# Main.net
KiCad netlist of a schematic drawn in Altium Designer
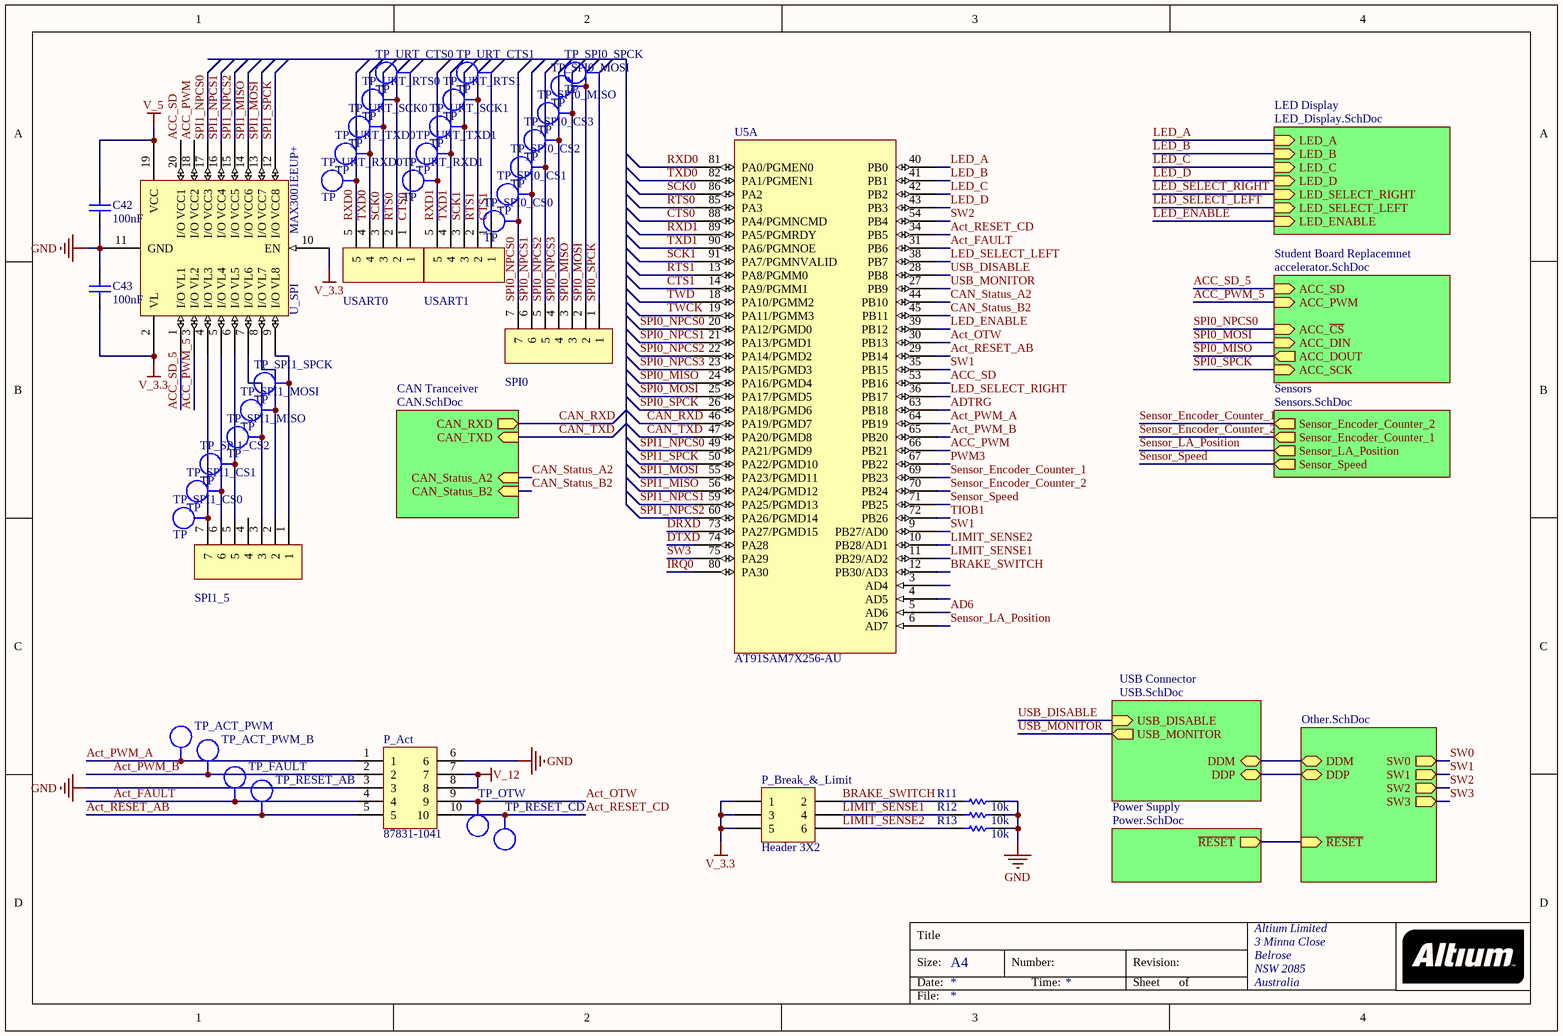
[diagram p0: Main.SchDoc]

(export (version "E")
  (design (tool "Eeschema 10.0.6"))
  (components
    (comp (ref "C42")
      (value "100nF")
      (footprint "0603")
      (description "CAP CER .10UF 50V X5R 0603")
      (fields (field (name "MANUFACTURER") "Taiyo Yuden") (field (name "PART NUMBER") "CP_100nF 0603"))
      (libsource (lib "ENEL429_4") (part "CP_100nF 0603"))
    )
    (comp (ref "C43")
      (value "100nF")
      (footprint "0603")
      (description "CAP CER .10UF 50V X5R 0603")
      (fields (field (name "MANUFACTURER") "Taiyo Yuden") (field (name "PART NUMBER") "CP_100nF 0603"))
      (libsource (lib "ENEL429_4") (part "CP_100nF 0603"))
    )
    (comp (ref "P_Act")
      (value "87831-1041")
      (footprint "87831-1041")
      (description "HEADER MALE 10POS VERT W/LOCK")
      (fields (field (name "MANUFACTURER") "Molex"))
      (libsource (lib "MarioLib") (part "87831-1041"))
    )
    (comp (ref "P_Break_&_Limit")
      (value "Header 3X2")
      (footprint "HDR2X3")
      (description "Header, 3-Pin, Dual row")
      (fields (field (name "PUBLISHER") "Altium Limited"))
      (libsource (lib "Miscellaneous Connectors") (part "Header 3X2"))
    )
    (comp (ref "R11")
      (value "10k")
      (footprint "0603")
      (description "RES 10.0K OHM 1/10W 1% 0603 SMD")
      (fields (field (name "MANUFACTURER") "Yageo") (field (name "PART NUMBER") "RS_10k 0603"))
      (libsource (lib "ENEL429_4") (part "RS_10k 0603"))
    )
    (comp (ref "R12")
      (value "10k")
      (footprint "0603")
      (description "RES 10.0K OHM 1/10W 1% 0603 SMD")
      (fields (field (name "MANUFACTURER") "Yageo") (field (name "PART NUMBER") "RS_10k 0603"))
      (libsource (lib "ENEL429_4") (part "RS_10k 0603"))
    )
    (comp (ref "R13")
      (value "10k")
      (footprint "0603")
      (description "RES 10.0K OHM 1/10W 1% 0603 SMD")
      (fields (field (name "MANUFACTURER") "Yageo") (field (name "PART NUMBER") "RS_10k 0603"))
      (libsource (lib "ENEL429_4") (part "RS_10k 0603"))
    )
    (comp (ref "SPI0")
      (value "53261-0771")
      (footprint "53261-0771")
      (description "7-pin PicoBlade Right-angle Header")
      (fields (field (name "MANUFACTURER") "Molex"))
      (libsource (lib "MarioLib") (part "53261-0771"))
    )
    (comp (ref "SPI1_5")
      (value "53261-0771")
      (footprint "53261-0771")
      (description "7-pin PicoBlade Right-angle Header")
      (fields (field (name "MANUFACTURER") "Molex"))
      (libsource (lib "MarioLib") (part "53261-0771"))
    )
    (comp (ref "TP_ACT_PWM")
      (value "TP")
      (footprint "TEST_POINT_4X2MM")
      (description "Test-Point")
      (fields (field (name "PART NUMBER") "TP_TESTPOINT"))
      (libsource (lib "ENEL429_4") (part "TP_TESTPOINT"))
    )
    (comp (ref "TP_ACT_PWM_B")
      (value "TP")
      (footprint "TEST_POINT_4X2MM")
      (description "Test-Point")
      (fields (field (name "PART NUMBER") "TP_TESTPOINT"))
      (libsource (lib "ENEL429_4") (part "TP_TESTPOINT"))
    )
    (comp (ref "TP_FAULT")
      (value "TP")
      (footprint "TEST_POINT_4X2MM")
      (description "Test-Point")
      (fields (field (name "PART NUMBER") "TP_TESTPOINT"))
      (libsource (lib "ENEL429_4") (part "TP_TESTPOINT"))
    )
    (comp (ref "TP_OTW")
      (value "TP")
      (footprint "TEST_POINT_4X2MM")
      (description "Test-Point")
      (fields (field (name "PART NUMBER") "TP_TESTPOINT"))
      (libsource (lib "ENEL429_4") (part "TP_TESTPOINT"))
    )
    (comp (ref "TP_RESET_AB")
      (value "TP")
      (footprint "TEST_POINT_4X2MM")
      (description "Test-Point")
      (fields (field (name "PART NUMBER") "TP_TESTPOINT"))
      (libsource (lib "ENEL429_4") (part "TP_TESTPOINT"))
    )
    (comp (ref "TP_RESET_CD")
      (value "TP")
      (footprint "TEST_POINT_4X2MM")
      (description "Test-Point")
      (fields (field (name "PART NUMBER") "TP_TESTPOINT"))
      (libsource (lib "ENEL429_4") (part "TP_TESTPOINT"))
    )
    (comp (ref "TP_SPI0_CS0")
      (value "TP")
      (footprint "TEST_POINT_4X2MM")
      (description "Test-Point")
      (fields (field (name "PART NUMBER") "TP_TESTPOINT"))
      (libsource (lib "ENEL429_4") (part "TP_TESTPOINT"))
    )
    (comp (ref "TP_SPI0_CS1")
      (value "TP")
      (footprint "TEST_POINT_4X2MM")
      (description "Test-Point")
      (fields (field (name "PART NUMBER") "TP_TESTPOINT"))
      (libsource (lib "ENEL429_4") (part "TP_TESTPOINT"))
    )
    (comp (ref "TP_SPI0_CS2")
      (value "TP")
      (footprint "TEST_POINT_4X2MM")
      (description "Test-Point")
      (fields (field (name "PART NUMBER") "TP_TESTPOINT"))
      (libsource (lib "ENEL429_4") (part "TP_TESTPOINT"))
    )
    (comp (ref "TP_SPI0_CS3")
      (value "TP")
      (footprint "TEST_POINT_4X2MM")
      (description "Test-Point")
      (fields (field (name "PART NUMBER") "TP_TESTPOINT"))
      (libsource (lib "ENEL429_4") (part "TP_TESTPOINT"))
    )
    (comp (ref "TP_SPI0_MISO")
      (value "TP")
      (footprint "TEST_POINT_4X2MM")
      (description "Test-Point")
      (fields (field (name "PART NUMBER") "TP_TESTPOINT"))
      (libsource (lib "ENEL429_4") (part "TP_TESTPOINT"))
    )
    (comp (ref "TP_SPI0_MOSI")
      (value "TP")
      (footprint "TEST_POINT_4X2MM")
      (description "Test-Point")
      (fields (field (name "PART NUMBER") "TP_TESTPOINT"))
      (libsource (lib "ENEL429_4") (part "TP_TESTPOINT"))
    )
    (comp (ref "TP_SPI0_SPCK")
      (value "TP")
      (footprint "TEST_POINT_4X2MM")
      (description "Test-Point")
      (fields (field (name "PART NUMBER") "TP_TESTPOINT"))
      (libsource (lib "ENEL429_4") (part "TP_TESTPOINT"))
    )
    (comp (ref "TP_SPI1_CS0")
      (value "TP")
      (footprint "TEST_POINT_4X2MM")
      (description "Test-Point")
      (fields (field (name "PART NUMBER") "TP_TESTPOINT"))
      (libsource (lib "ENEL429_4") (part "TP_TESTPOINT"))
    )
    (comp (ref "TP_SPI1_CS1")
      (value "TP")
      (footprint "TEST_POINT_4X2MM")
      (description "Test-Point")
      (fields (field (name "PART NUMBER") "TP_TESTPOINT"))
      (libsource (lib "ENEL429_4") (part "TP_TESTPOINT"))
    )
    (comp (ref "TP_SPI1_CS2")
      (value "TP")
      (footprint "TEST_POINT_4X2MM")
      (description "Test-Point")
      (fields (field (name "PART NUMBER") "TP_TESTPOINT"))
      (libsource (lib "ENEL429_4") (part "TP_TESTPOINT"))
    )
    (comp (ref "TP_SPI1_MISO")
      (value "TP")
      (footprint "TEST_POINT_4X2MM")
      (description "Test-Point")
      (fields (field (name "PART NUMBER") "TP_TESTPOINT"))
      (libsource (lib "ENEL429_4") (part "TP_TESTPOINT"))
    )
    (comp (ref "TP_SPI1_MOSI")
      (value "TP")
      (footprint "TEST_POINT_4X2MM")
      (description "Test-Point")
      (fields (field (name "PART NUMBER") "TP_TESTPOINT"))
      (libsource (lib "ENEL429_4") (part "TP_TESTPOINT"))
    )
    (comp (ref "TP_SPI1_SPCK")
      (value "TP")
      (footprint "TEST_POINT_4X2MM")
      (description "Test-Point")
      (fields (field (name "PART NUMBER") "TP_TESTPOINT"))
      (libsource (lib "ENEL429_4") (part "TP_TESTPOINT"))
    )
    (comp (ref "TP_URT_CTS0")
      (value "TP")
      (footprint "TEST_POINT_4X2MM")
      (description "Test-Point")
      (fields (field (name "PART NUMBER") "TP_TESTPOINT"))
      (libsource (lib "ENEL429_4") (part "TP_TESTPOINT"))
    )
    (comp (ref "TP_URT_CTS1")
      (value "TP")
      (footprint "TEST_POINT_4X2MM")
      (description "Test-Point")
      (fields (field (name "PART NUMBER") "TP_TESTPOINT"))
      (libsource (lib "ENEL429_4") (part "TP_TESTPOINT"))
    )
    (comp (ref "TP_URT_RTS0")
      (value "TP")
      (footprint "TEST_POINT_4X2MM")
      (description "Test-Point")
      (fields (field (name "PART NUMBER") "TP_TESTPOINT"))
      (libsource (lib "ENEL429_4") (part "TP_TESTPOINT"))
    )
    (comp (ref "TP_URT_RTS1")
      (value "TP")
      (footprint "TEST_POINT_4X2MM")
      (description "Test-Point")
      (fields (field (name "PART NUMBER") "TP_TESTPOINT"))
      (libsource (lib "ENEL429_4") (part "TP_TESTPOINT"))
    )
    (comp (ref "TP_URT_RXD0")
      (value "TP")
      (footprint "TEST_POINT_4X2MM")
      (description "Test-Point")
      (fields (field (name "PART NUMBER") "TP_TESTPOINT"))
      (libsource (lib "ENEL429_4") (part "TP_TESTPOINT"))
    )
    (comp (ref "TP_URT_RXD1")
      (value "TP")
      (footprint "TEST_POINT_4X2MM")
      (description "Test-Point")
      (fields (field (name "PART NUMBER") "TP_TESTPOINT"))
      (libsource (lib "ENEL429_4") (part "TP_TESTPOINT"))
    )
    (comp (ref "TP_URT_SCK0")
      (value "TP")
      (footprint "TEST_POINT_4X2MM")
      (description "Test-Point")
      (fields (field (name "PART NUMBER") "TP_TESTPOINT"))
      (libsource (lib "ENEL429_4") (part "TP_TESTPOINT"))
    )
    (comp (ref "TP_URT_SCK1")
      (value "TP")
      (footprint "TEST_POINT_4X2MM")
      (description "Test-Point")
      (fields (field (name "PART NUMBER") "TP_TESTPOINT"))
      (libsource (lib "ENEL429_4") (part "TP_TESTPOINT"))
    )
    (comp (ref "TP_URT_TXD0")
      (value "TP")
      (footprint "TEST_POINT_4X2MM")
      (description "Test-Point")
      (fields (field (name "PART NUMBER") "TP_TESTPOINT"))
      (libsource (lib "ENEL429_4") (part "TP_TESTPOINT"))
    )
    (comp (ref "TP_URT_TXD1")
      (value "TP")
      (footprint "TEST_POINT_4X2MM")
      (description "Test-Point")
      (fields (field (name "PART NUMBER") "TP_TESTPOINT"))
      (libsource (lib "ENEL429_4") (part "TP_TESTPOINT"))
    )
    (comp (ref "U5")
      (value "AT91SAM7X256-AU")
      (footprint "LQFP100_N")
      (description "ARM7TDMI 32-Bit RISC CPU 256KB Flash and 64KB SRAM")
      (fields
        (field (name "MANAFACTURE PART NUMBER") "AT91SAM7XC256B-AU")
        (field (name "PUBLISHER") "Altium Limited")
      )
      (libsource (lib "Atmel Microcontroller 32-Bit ARM") (part "AT91SAM7X256-AU"))
    )
    (comp (ref "USART0")
      (value "53261-0571")
      (footprint "53261-0571")
      (description "5-pin PicoBlade Right-angle Header")
      (fields (field (name "MANUFACTURER") "Molex"))
      (libsource (lib "MarioLib") (part "53261-0571"))
    )
    (comp (ref "USART1")
      (value "53261-0571")
      (footprint "53261-0571")
      (description "5-pin PicoBlade Right-angle Header")
      (fields (field (name "MANUFACTURER") "Molex"))
      (libsource (lib "MarioLib") (part "53261-0571"))
    )
    (comp (ref "U_SPI")
      (value "MAX3001EEUP+")
      (footprint "TSOP65P640X110-20N")
      (libsource (lib "MarioLib") (part "MAX3001EEUP+"))
    )
  )
  (nets
    (net (code "1") (name "/ACC_PWM") (class "Default")
      (node (ref "U5") (pin "66") (pinfunction "PB21_66") (pintype "bidirectional"))
      (node (ref "U_SPI") (pin "18") (pinfunction "I/O_VCC2_18") (pintype "bidirectional"))
    )
    (net (code "2") (name "/ACC_PWM_5") (class "Default")
      (node (ref "U_SPI") (pin "3") (pinfunction "I/O_VL2_3") (pintype "bidirectional"))
    )
    (net (code "3") (name "/ACC_SD") (class "Default")
      (node (ref "U5") (pin "53") (pinfunction "PB16_53") (pintype "bidirectional"))
      (node (ref "U_SPI") (pin "20") (pinfunction "I/O_VCC1_20") (pintype "bidirectional"))
    )
    (net (code "4") (name "/ACC_SD_5") (class "Default")
      (node (ref "U_SPI") (pin "1") (pinfunction "I/O_VL1_1") (pintype "bidirectional"))
    )
    (net (code "5") (name "/AD6") (class "Default")
      (node (ref "U5") (pin "5") (pinfunction "AD6_5") (pintype "input"))
    )
    (net (code "6") (name "/ADTRG") (class "Default")
      (node (ref "U5") (pin "63") (pinfunction "PB18_63") (pintype "bidirectional"))
    )
    (net (code "7") (name "/Act_FAULT") (class "Default")
      (node (ref "P_Act") (pin "4") (pinfunction "4_4") (pintype "passive"))
      (node (ref "TP_FAULT") (pin "1") (pinfunction "1_1") (pintype "passive"))
      (node (ref "U5") (pin "31") (pinfunction "PB6_31") (pintype "bidirectional"))
    )
    (net (code "8") (name "/Act_OTW") (class "Default")
      (node (ref "P_Act") (pin "9") (pinfunction "9_9") (pintype "passive"))
      (node (ref "TP_OTW") (pin "1") (pinfunction "1_1") (pintype "passive"))
      (node (ref "U5") (pin "30") (pinfunction "PB13_30") (pintype "bidirectional"))
    )
    (net (code "9") (name "/Act_PWM_A") (class "Default")
      (node (ref "P_Act") (pin "1") (pinfunction "1_1") (pintype "passive"))
      (node (ref "TP_ACT_PWM") (pin "1") (pinfunction "1_1") (pintype "passive"))
      (node (ref "U5") (pin "64") (pinfunction "PB19_64") (pintype "bidirectional"))
    )
    (net (code "10") (name "/Act_PWM_B") (class "Default")
      (node (ref "P_Act") (pin "2") (pinfunction "2_2") (pintype "passive"))
      (node (ref "TP_ACT_PWM_B") (pin "1") (pinfunction "1_1") (pintype "passive"))
      (node (ref "U5") (pin "65") (pinfunction "PB20_65") (pintype "bidirectional"))
    )
    (net (code "11") (name "/Act_RESET_AB") (class "Default")
      (node (ref "P_Act") (pin "5") (pinfunction "5_5") (pintype "passive"))
      (node (ref "TP_RESET_AB") (pin "1") (pinfunction "1_1") (pintype "passive"))
      (node (ref "U5") (pin "29") (pinfunction "PB14_29") (pintype "bidirectional"))
    )
    (net (code "12") (name "/Act_RESET_CD") (class "Default")
      (node (ref "P_Act") (pin "10") (pinfunction "10_10") (pintype "passive"))
      (node (ref "TP_RESET_CD") (pin "1") (pinfunction "1_1") (pintype "passive"))
      (node (ref "U5") (pin "34") (pinfunction "PB5_34") (pintype "bidirectional"))
    )
    (net (code "13") (name "/BRAKE_SWITCH") (class "Default")
      (node (ref "P_Break_&_Limit") (pin "2") (pinfunction "2_2") (pintype "passive"))
      (node (ref "R11") (pin "1") (pinfunction "1_1") (pintype "passive"))
      (node (ref "U5") (pin "12") (pinfunction "PB30/AD3_12") (pintype "bidirectional"))
    )
    (net (code "14") (name "/CAN_RXD") (class "Default")
      (node (ref "U5") (pin "46") (pinfunction "PA19/PGMD7_46") (pintype "bidirectional"))
    )
    (net (code "15") (name "/CAN_Status_A2") (class "Default")
      (node (ref "U5") (pin "44") (pinfunction "PB10_44") (pintype "bidirectional"))
    )
    (net (code "16") (name "/CAN_Status_B2") (class "Default")
      (node (ref "U5") (pin "45") (pinfunction "PB11_45") (pintype "bidirectional"))
    )
    (net (code "17") (name "/CAN_TXD") (class "Default")
      (node (ref "U5") (pin "47") (pinfunction "PA20/PGMD8_47") (pintype "bidirectional"))
    )
    (net (code "18") (name "/CTS0") (class "Default")
      (node (ref "TP_URT_CTS0") (pin "1") (pinfunction "1_1") (pintype "passive"))
      (node (ref "U5") (pin "88") (pinfunction "PA4/PGMNCMD_88") (pintype "bidirectional"))
      (node (ref "USART0") (pin "1") (pinfunction "1_1") (pintype "passive"))
    )
    (net (code "19") (name "/CTS1") (class "Default")
      (node (ref "TP_URT_CTS1") (pin "1") (pinfunction "1_1") (pintype "passive"))
      (node (ref "U5") (pin "14") (pinfunction "PA9/PGMM1_14") (pintype "bidirectional"))
      (node (ref "USART1") (pin "1") (pinfunction "1_1") (pintype "passive"))
    )
    (net (code "22") (name "/DRXD") (class "Default")
      (node (ref "U5") (pin "73") (pinfunction "PA27/PGMD15_73") (pintype "bidirectional"))
    )
    (net (code "23") (name "/DTXD") (class "Default")
      (node (ref "U5") (pin "74") (pinfunction "PA28_74") (pintype "bidirectional"))
    )
    (net (code "24") (name "/IRQ0") (class "Default")
      (node (ref "U5") (pin "80") (pinfunction "PA30_80") (pintype "bidirectional"))
    )
    (net (code "25") (name "/LED_A") (class "Default")
      (node (ref "U5") (pin "40") (pinfunction "PB0_40") (pintype "bidirectional"))
    )
    (net (code "26") (name "/LED_B") (class "Default")
      (node (ref "U5") (pin "41") (pinfunction "PB1_41") (pintype "bidirectional"))
    )
    (net (code "27") (name "/LED_C") (class "Default")
      (node (ref "U5") (pin "42") (pinfunction "PB2_42") (pintype "bidirectional"))
    )
    (net (code "28") (name "/LED_D") (class "Default")
      (node (ref "U5") (pin "43") (pinfunction "PB3_43") (pintype "bidirectional"))
    )
    (net (code "29") (name "/LED_ENABLE") (class "Default")
      (node (ref "U5") (pin "39") (pinfunction "PB12_39") (pintype "bidirectional"))
    )
    (net (code "30") (name "/LED_SELECT_LEFT") (class "Default")
      (node (ref "U5") (pin "38") (pinfunction "PB7_38") (pintype "bidirectional"))
    )
    (net (code "31") (name "/LED_SELECT_RIGHT") (class "Default")
      (node (ref "U5") (pin "36") (pinfunction "PB17_36") (pintype "bidirectional"))
    )
    (net (code "32") (name "/LIMIT_SENSE1") (class "Default")
      (node (ref "P_Break_&_Limit") (pin "4") (pinfunction "4_4") (pintype "passive"))
      (node (ref "R12") (pin "1") (pinfunction "1_1") (pintype "passive"))
      (node (ref "U5") (pin "11") (pinfunction "PB29/AD2_11") (pintype "bidirectional"))
    )
    (net (code "33") (name "/LIMIT_SENSE2") (class "Default")
      (node (ref "P_Break_&_Limit") (pin "6") (pinfunction "6_6") (pintype "passive"))
      (node (ref "R13") (pin "1") (pinfunction "1_1") (pintype "passive"))
      (node (ref "U5") (pin "10") (pinfunction "PB28/AD1_10") (pintype "bidirectional"))
    )
    (net (code "34") (name "/PWM3") (class "Default")
      (node (ref "U5") (pin "67") (pinfunction "PB22_67") (pintype "bidirectional"))
    )
    (net (code "35") (name "/RTS0") (class "Default")
      (node (ref "TP_URT_RTS0") (pin "1") (pinfunction "1_1") (pintype "passive"))
      (node (ref "U5") (pin "85") (pinfunction "PA3_85") (pintype "bidirectional"))
      (node (ref "USART0") (pin "2") (pinfunction "2_2") (pintype "passive"))
    )
    (net (code "36") (name "/RTS1") (class "Default")
      (node (ref "TP_URT_RTS1") (pin "1") (pinfunction "1_1") (pintype "passive"))
      (node (ref "U5") (pin "13") (pinfunction "PA8/PGMM0_13") (pintype "bidirectional"))
      (node (ref "USART1") (pin "2") (pinfunction "2_2") (pintype "passive"))
    )
    (net (code "37") (name "/RXD0") (class "Default")
      (node (ref "TP_URT_RXD0") (pin "1") (pinfunction "1_1") (pintype "passive"))
      (node (ref "U5") (pin "81") (pinfunction "PA0/PGMEN0_81") (pintype "bidirectional"))
      (node (ref "USART0") (pin "5") (pinfunction "5_5") (pintype "passive"))
    )
    (net (code "38") (name "/RXD1") (class "Default")
      (node (ref "TP_URT_RXD1") (pin "1") (pinfunction "1_1") (pintype "passive"))
      (node (ref "U5") (pin "89") (pinfunction "PA5/PGMRDY_89") (pintype "bidirectional"))
      (node (ref "USART1") (pin "5") (pinfunction "5_5") (pintype "passive"))
    )
    (net (code "39") (name "/SCK0") (class "Default")
      (node (ref "TP_URT_SCK0") (pin "1") (pinfunction "1_1") (pintype "passive"))
      (node (ref "U5") (pin "86") (pinfunction "PA2_86") (pintype "bidirectional"))
      (node (ref "USART0") (pin "3") (pinfunction "3_3") (pintype "passive"))
    )
    (net (code "40") (name "/SCK1") (class "Default")
      (node (ref "TP_URT_SCK1") (pin "1") (pinfunction "1_1") (pintype "passive"))
      (node (ref "U5") (pin "91") (pinfunction "PA7/PGMNVALID_91") (pintype "bidirectional"))
      (node (ref "USART1") (pin "3") (pinfunction "3_3") (pintype "passive"))
    )
    (net (code "41") (name "/SPI0_MISO") (class "Default")
      (node (ref "SPI0") (pin "3") (pinfunction "3_3") (pintype "passive"))
      (node (ref "TP_SPI0_MISO") (pin "1") (pinfunction "1_1") (pintype "passive"))
      (node (ref "U5") (pin "24") (pinfunction "PA16/PGMD4_24") (pintype "bidirectional"))
    )
    (net (code "42") (name "/SPI0_MOSI") (class "Default")
      (node (ref "SPI0") (pin "2") (pinfunction "2_2") (pintype "passive"))
      (node (ref "TP_SPI0_MOSI") (pin "1") (pinfunction "1_1") (pintype "passive"))
      (node (ref "U5") (pin "25") (pinfunction "PA17/PGMD5_25") (pintype "bidirectional"))
    )
    (net (code "43") (name "/SPI0_NPCS0") (class "Default")
      (node (ref "SPI0") (pin "7") (pinfunction "7_7") (pintype "passive"))
      (node (ref "TP_SPI0_CS0") (pin "1") (pinfunction "1_1") (pintype "passive"))
      (node (ref "U5") (pin "20") (pinfunction "PA12/PGMD0_20") (pintype "bidirectional"))
    )
    (net (code "44") (name "/SPI0_NPCS1") (class "Default")
      (node (ref "SPI0") (pin "6") (pinfunction "6_6") (pintype "passive"))
      (node (ref "TP_SPI0_CS1") (pin "1") (pinfunction "1_1") (pintype "passive"))
      (node (ref "U5") (pin "21") (pinfunction "PA13/PGMD1_21") (pintype "bidirectional"))
    )
    (net (code "45") (name "/SPI0_NPCS2") (class "Default")
      (node (ref "SPI0") (pin "5") (pinfunction "5_5") (pintype "passive"))
      (node (ref "TP_SPI0_CS2") (pin "1") (pinfunction "1_1") (pintype "passive"))
      (node (ref "U5") (pin "22") (pinfunction "PA14/PGMD2_22") (pintype "bidirectional"))
    )
    (net (code "46") (name "/SPI0_NPCS3") (class "Default")
      (node (ref "SPI0") (pin "4") (pinfunction "4_4") (pintype "passive"))
      (node (ref "TP_SPI0_CS3") (pin "1") (pinfunction "1_1") (pintype "passive"))
      (node (ref "U5") (pin "23") (pinfunction "PA15/PGMD3_23") (pintype "bidirectional"))
    )
    (net (code "47") (name "/SPI0_SPCK") (class "Default")
      (node (ref "SPI0") (pin "1") (pinfunction "1_1") (pintype "passive"))
      (node (ref "TP_SPI0_SPCK") (pin "1") (pinfunction "1_1") (pintype "passive"))
      (node (ref "U5") (pin "26") (pinfunction "PA18/PGMD6_26") (pintype "bidirectional"))
    )
    (net (code "48") (name "/SPI1_MISO") (class "Default")
      (node (ref "U5") (pin "56") (pinfunction "PA24/PGMD12_56") (pintype "bidirectional"))
      (node (ref "U_SPI") (pin "14") (pinfunction "I/O_VCC6_14") (pintype "bidirectional"))
    )
    (net (code "49") (name "/SPI1_MOSI") (class "Default")
      (node (ref "U5") (pin "55") (pinfunction "PA23/PGMD11_55") (pintype "bidirectional"))
      (node (ref "U_SPI") (pin "13") (pinfunction "I/O_VCC7_13") (pintype "bidirectional"))
    )
    (net (code "50") (name "/SPI1_NPCS0") (class "Default")
      (node (ref "U5") (pin "49") (pinfunction "PA21/PGMD9_49") (pintype "bidirectional"))
      (node (ref "U_SPI") (pin "17") (pinfunction "I/O_VCC3_17") (pintype "bidirectional"))
    )
    (net (code "51") (name "/SPI1_NPCS1") (class "Default")
      (node (ref "U5") (pin "59") (pinfunction "PA25/PGMD13_59") (pintype "bidirectional"))
      (node (ref "U_SPI") (pin "16") (pinfunction "I/O_VCC4_16") (pintype "bidirectional"))
    )
    (net (code "52") (name "/SPI1_NPCS2") (class "Default")
      (node (ref "U5") (pin "60") (pinfunction "PA26/PGMD14_60") (pintype "bidirectional"))
      (node (ref "U_SPI") (pin "15") (pinfunction "I/O_VCC5_15") (pintype "bidirectional"))
    )
    (net (code "53") (name "/SPI1_SPCK") (class "Default")
      (node (ref "U5") (pin "50") (pinfunction "PA22/PGMD10_50") (pintype "bidirectional"))
      (node (ref "U_SPI") (pin "12") (pinfunction "I/O_VCC8_12") (pintype "bidirectional"))
    )
    (net (code "55") (name "/SW1") (class "Default")
      (node (ref "U5") (pin "35") (pinfunction "PB15_35") (pintype "bidirectional"))
      (node (ref "U5") (pin "9") (pinfunction "PB27/AD0_9") (pintype "bidirectional"))
    )
    (net (code "56") (name "/SW2") (class "Default")
      (node (ref "U5") (pin "54") (pinfunction "PB4_54") (pintype "bidirectional"))
    )
    (net (code "57") (name "/SW3") (class "Default")
      (node (ref "U5") (pin "75") (pinfunction "PA29_75") (pintype "bidirectional"))
    )
    (net (code "58") (name "/Sensor_Encoder_Counter_1") (class "Default")
      (node (ref "U5") (pin "69") (pinfunction "PB23_69") (pintype "bidirectional"))
    )
    (net (code "59") (name "/Sensor_Encoder_Counter_2") (class "Default")
      (node (ref "U5") (pin "70") (pinfunction "PB24_70") (pintype "bidirectional"))
    )
    (net (code "60") (name "/Sensor_LA_Position") (class "Default")
      (node (ref "U5") (pin "6") (pinfunction "AD7_6") (pintype "input"))
    )
    (net (code "61") (name "/Sensor_Speed") (class "Default")
      (node (ref "U5") (pin "71") (pinfunction "PB25_71") (pintype "bidirectional"))
    )
    (net (code "62") (name "/TIOB1") (class "Default")
      (node (ref "U5") (pin "72") (pinfunction "PB26_72") (pintype "bidirectional"))
    )
    (net (code "63") (name "/TWCK") (class "Default")
      (node (ref "U5") (pin "19") (pinfunction "PA11/PGMM3_19") (pintype "bidirectional"))
    )
    (net (code "64") (name "/TWD") (class "Default")
      (node (ref "U5") (pin "18") (pinfunction "PA10/PGMM2_18") (pintype "bidirectional"))
    )
    (net (code "65") (name "/TXD0") (class "Default")
      (node (ref "TP_URT_TXD0") (pin "1") (pinfunction "1_1") (pintype "passive"))
      (node (ref "U5") (pin "82") (pinfunction "PA1/PGMEN1_82") (pintype "bidirectional"))
      (node (ref "USART0") (pin "4") (pinfunction "4_4") (pintype "passive"))
    )
    (net (code "66") (name "/TXD1") (class "Default")
      (node (ref "TP_URT_TXD1") (pin "1") (pinfunction "1_1") (pintype "passive"))
      (node (ref "U5") (pin "90") (pinfunction "PA6/PGMNOE_90") (pintype "bidirectional"))
      (node (ref "USART1") (pin "4") (pinfunction "4_4") (pintype "passive"))
    )
    (net (code "67") (name "/USB_DISABLE") (class "Default")
      (node (ref "U5") (pin "28") (pinfunction "PB8_28") (pintype "bidirectional"))
    )
    (net (code "68") (name "/USB_MONITOR") (class "Default")
      (node (ref "U5") (pin "27") (pinfunction "PB9_27") (pintype "bidirectional"))
    )
    (net (code "70") (name "GND") (class "Default")
      (node (ref "C42") (pin "1") (pinfunction "1_1") (pintype "passive"))
      (node (ref "C43") (pin "2") (pinfunction "2_2") (pintype "passive"))
      (node (ref "P_Act") (pin "3") (pinfunction "3_3") (pintype "passive"))
      (node (ref "P_Act") (pin "6") (pinfunction "6_6") (pintype "passive"))
      (node (ref "R11") (pin "2") (pinfunction "2_2") (pintype "passive"))
      (node (ref "R12") (pin "2") (pinfunction "2_2") (pintype "passive"))
      (node (ref "R13") (pin "2") (pinfunction "2_2") (pintype "passive"))
      (node (ref "U_SPI") (pin "11") (pinfunction "GND_11") (pintype "passive"))
    )
    (net (code "71") (name "Net-(U_SPI-I{slash}O_VL3)") (class "Default")
      (node (ref "SPI1_5") (pin "7") (pinfunction "7_7") (pintype "passive"))
      (node (ref "TP_SPI1_CS0") (pin "1") (pinfunction "1_1") (pintype "passive"))
      (node (ref "U_SPI") (pin "4") (pinfunction "I/O_VL3_4") (pintype "bidirectional"))
    )
    (net (code "72") (name "Net-(U_SPI-I{slash}O_VL4)") (class "Default")
      (node (ref "SPI1_5") (pin "6") (pinfunction "6_6") (pintype "passive"))
      (node (ref "TP_SPI1_CS1") (pin "1") (pinfunction "1_1") (pintype "passive"))
      (node (ref "U_SPI") (pin "5") (pinfunction "I/O_VL4_5") (pintype "bidirectional"))
    )
    (net (code "73") (name "Net-(U_SPI-I{slash}O_VL5)") (class "Default")
      (node (ref "SPI1_5") (pin "5") (pinfunction "5_5") (pintype "passive"))
      (node (ref "TP_SPI1_CS2") (pin "1") (pinfunction "1_1") (pintype "passive"))
      (node (ref "U_SPI") (pin "6") (pinfunction "I/O_VL5_6") (pintype "bidirectional"))
    )
    (net (code "74") (name "Net-(U_SPI-I{slash}O_VL6)") (class "Default")
      (node (ref "SPI1_5") (pin "3") (pinfunction "3_3") (pintype "passive"))
      (node (ref "TP_SPI1_MISO") (pin "1") (pinfunction "1_1") (pintype "passive"))
      (node (ref "U_SPI") (pin "7") (pinfunction "I/O_VL6_7") (pintype "bidirectional"))
    )
    (net (code "75") (name "Net-(U_SPI-I{slash}O_VL7)") (class "Default")
      (node (ref "SPI1_5") (pin "2") (pinfunction "2_2") (pintype "passive"))
      (node (ref "TP_SPI1_MOSI") (pin "1") (pinfunction "1_1") (pintype "passive"))
      (node (ref "U_SPI") (pin "8") (pinfunction "I/O_VL7_8") (pintype "bidirectional"))
    )
    (net (code "76") (name "Net-(U_SPI-I{slash}O_VL8)") (class "Default")
      (node (ref "SPI1_5") (pin "1") (pinfunction "1_1") (pintype "passive"))
      (node (ref "TP_SPI1_SPCK") (pin "1") (pinfunction "1_1") (pintype "passive"))
      (node (ref "U_SPI") (pin "9") (pinfunction "I/O_VL8_9") (pintype "bidirectional"))
    )
    (net (code "77") (name "V_3.3") (class "Default")
      (node (ref "C43") (pin "1") (pinfunction "1_1") (pintype "passive"))
      (node (ref "P_Break_&_Limit") (pin "1") (pinfunction "1_1") (pintype "passive"))
      (node (ref "P_Break_&_Limit") (pin "3") (pinfunction "3_3") (pintype "passive"))
      (node (ref "P_Break_&_Limit") (pin "5") (pinfunction "5_5") (pintype "passive"))
      (node (ref "U_SPI") (pin "10") (pinfunction "EN_10") (pintype "input"))
      (node (ref "U_SPI") (pin "2") (pinfunction "VL_2") (pintype "power_in"))
    )
    (net (code "78") (name "V_5") (class "Default")
      (node (ref "C42") (pin "2") (pinfunction "2_2") (pintype "passive"))
      (node (ref "U_SPI") (pin "19") (pinfunction "VCC_19") (pintype "power_in"))
    )
    (net (code "79") (name "V_12") (class "Default")
      (node (ref "P_Act") (pin "7") (pinfunction "7_7") (pintype "passive"))
      (node (ref "P_Act") (pin "8") (pinfunction "8_8") (pintype "passive"))
    )
    (net (code "80") (name "unconnected-(SPI1_5-Pad4)") (class "Default")
      (node (ref "SPI1_5") (pin "4") (pinfunction "4_4") (pintype "passive"))
    )
    (net (code "81") (name "unconnected-(U5A-AD4-Pad3)") (class "Default")
      (node (ref "U5") (pin "3") (pinfunction "AD4_3") (pintype "input"))
    )
    (net (code "82") (name "unconnected-(U5A-AD5-Pad4)") (class "Default")
      (node (ref "U5") (pin "4") (pinfunction "AD5_4") (pintype "input"))
    )
  )
)
